# caton-self-test.net
KiCad netlist of a schematic drawn in Altium Designer
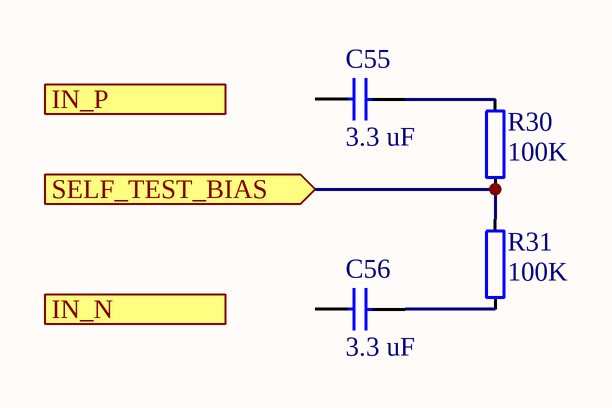
[diagram p0: caton-self-test.SchDoc]

(export (version "E")
  (design (tool "Eeschema 10.0.6"))
  (components
    (comp (ref "C55")
      (value "3.3 uF")
      (footprint "BWRC:0402")
      (description "Capacitor, 0402, X5R, ±20%")
      (fields
        (field (name "PART NUMBER") "C0402-4µ7")
        (field (name "MANUFACTURER") "N.A.")
        (field (name "AUTHOR") "rsk")
      )
      (libsource (lib "BSAC") (part "C0402"))
    )
    (comp (ref "C56")
      (value "3.3 uF")
      (footprint "BWRC:0402")
      (description "Capacitor, 0402, X5R, ±20%")
      (fields
        (field (name "PART NUMBER") "C0402-4µ7")
        (field (name "MANUFACTURER") "N.A.")
        (field (name "AUTHOR") "rsk")
      )
      (libsource (lib "BSAC") (part "C0402"))
    )
    (comp (ref "R30")
      (value "100K")
      (footprint "BWRC:0402")
      (description "Resistor, 0402, ±1%, 0.05W")
      (fields
        (field (name "PART NUMBER") "R0201-10k")
        (field (name "MANUFACTURER") "N.A.")
        (field (name "AUTHOR") "rsk")
      )
      (libsource (lib "BSAC") (part "R0402"))
    )
    (comp (ref "R31")
      (value "100K")
      (footprint "BWRC:0402")
      (description "Resistor, 0402, ±1%, 0.05W")
      (fields
        (field (name "PART NUMBER") "R0201-10k")
        (field (name "MANUFACTURER") "N.A.")
        (field (name "AUTHOR") "rsk")
      )
      (libsource (lib "BSAC") (part "R0402"))
    )
  )
  (nets
    (net (code "3") (name "/SELF_TEST_BIAS") (class "Default")
      (node (ref "R30") (pin "1") (pinfunction "1_1") (pintype "passive"))
      (node (ref "R31") (pin "2") (pinfunction "2_2") (pintype "passive"))
    )
    (net (code "4") (name "Net-(C55-Pad2)") (class "Default")
      (node (ref "C55") (pin "2") (pinfunction "2_2") (pintype "passive"))
      (node (ref "R30") (pin "2") (pinfunction "2_2") (pintype "passive"))
    )
    (net (code "5") (name "Net-(C56-Pad2)") (class "Default")
      (node (ref "C56") (pin "2") (pinfunction "2_2") (pintype "passive"))
      (node (ref "R31") (pin "1") (pinfunction "1_1") (pintype "passive"))
    )
    (net (code "6") (name "unconnected-(C55-Pad1)") (class "Default")
      (node (ref "C55") (pin "1") (pinfunction "1_1") (pintype "passive"))
    )
    (net (code "7") (name "unconnected-(C56-Pad1)") (class "Default")
      (node (ref "C56") (pin "1") (pinfunction "1_1") (pintype "passive"))
    )
  )
)
